# CE842170047_SHEET2.net
KiCad netlist of a schematic drawn in Altium Designer
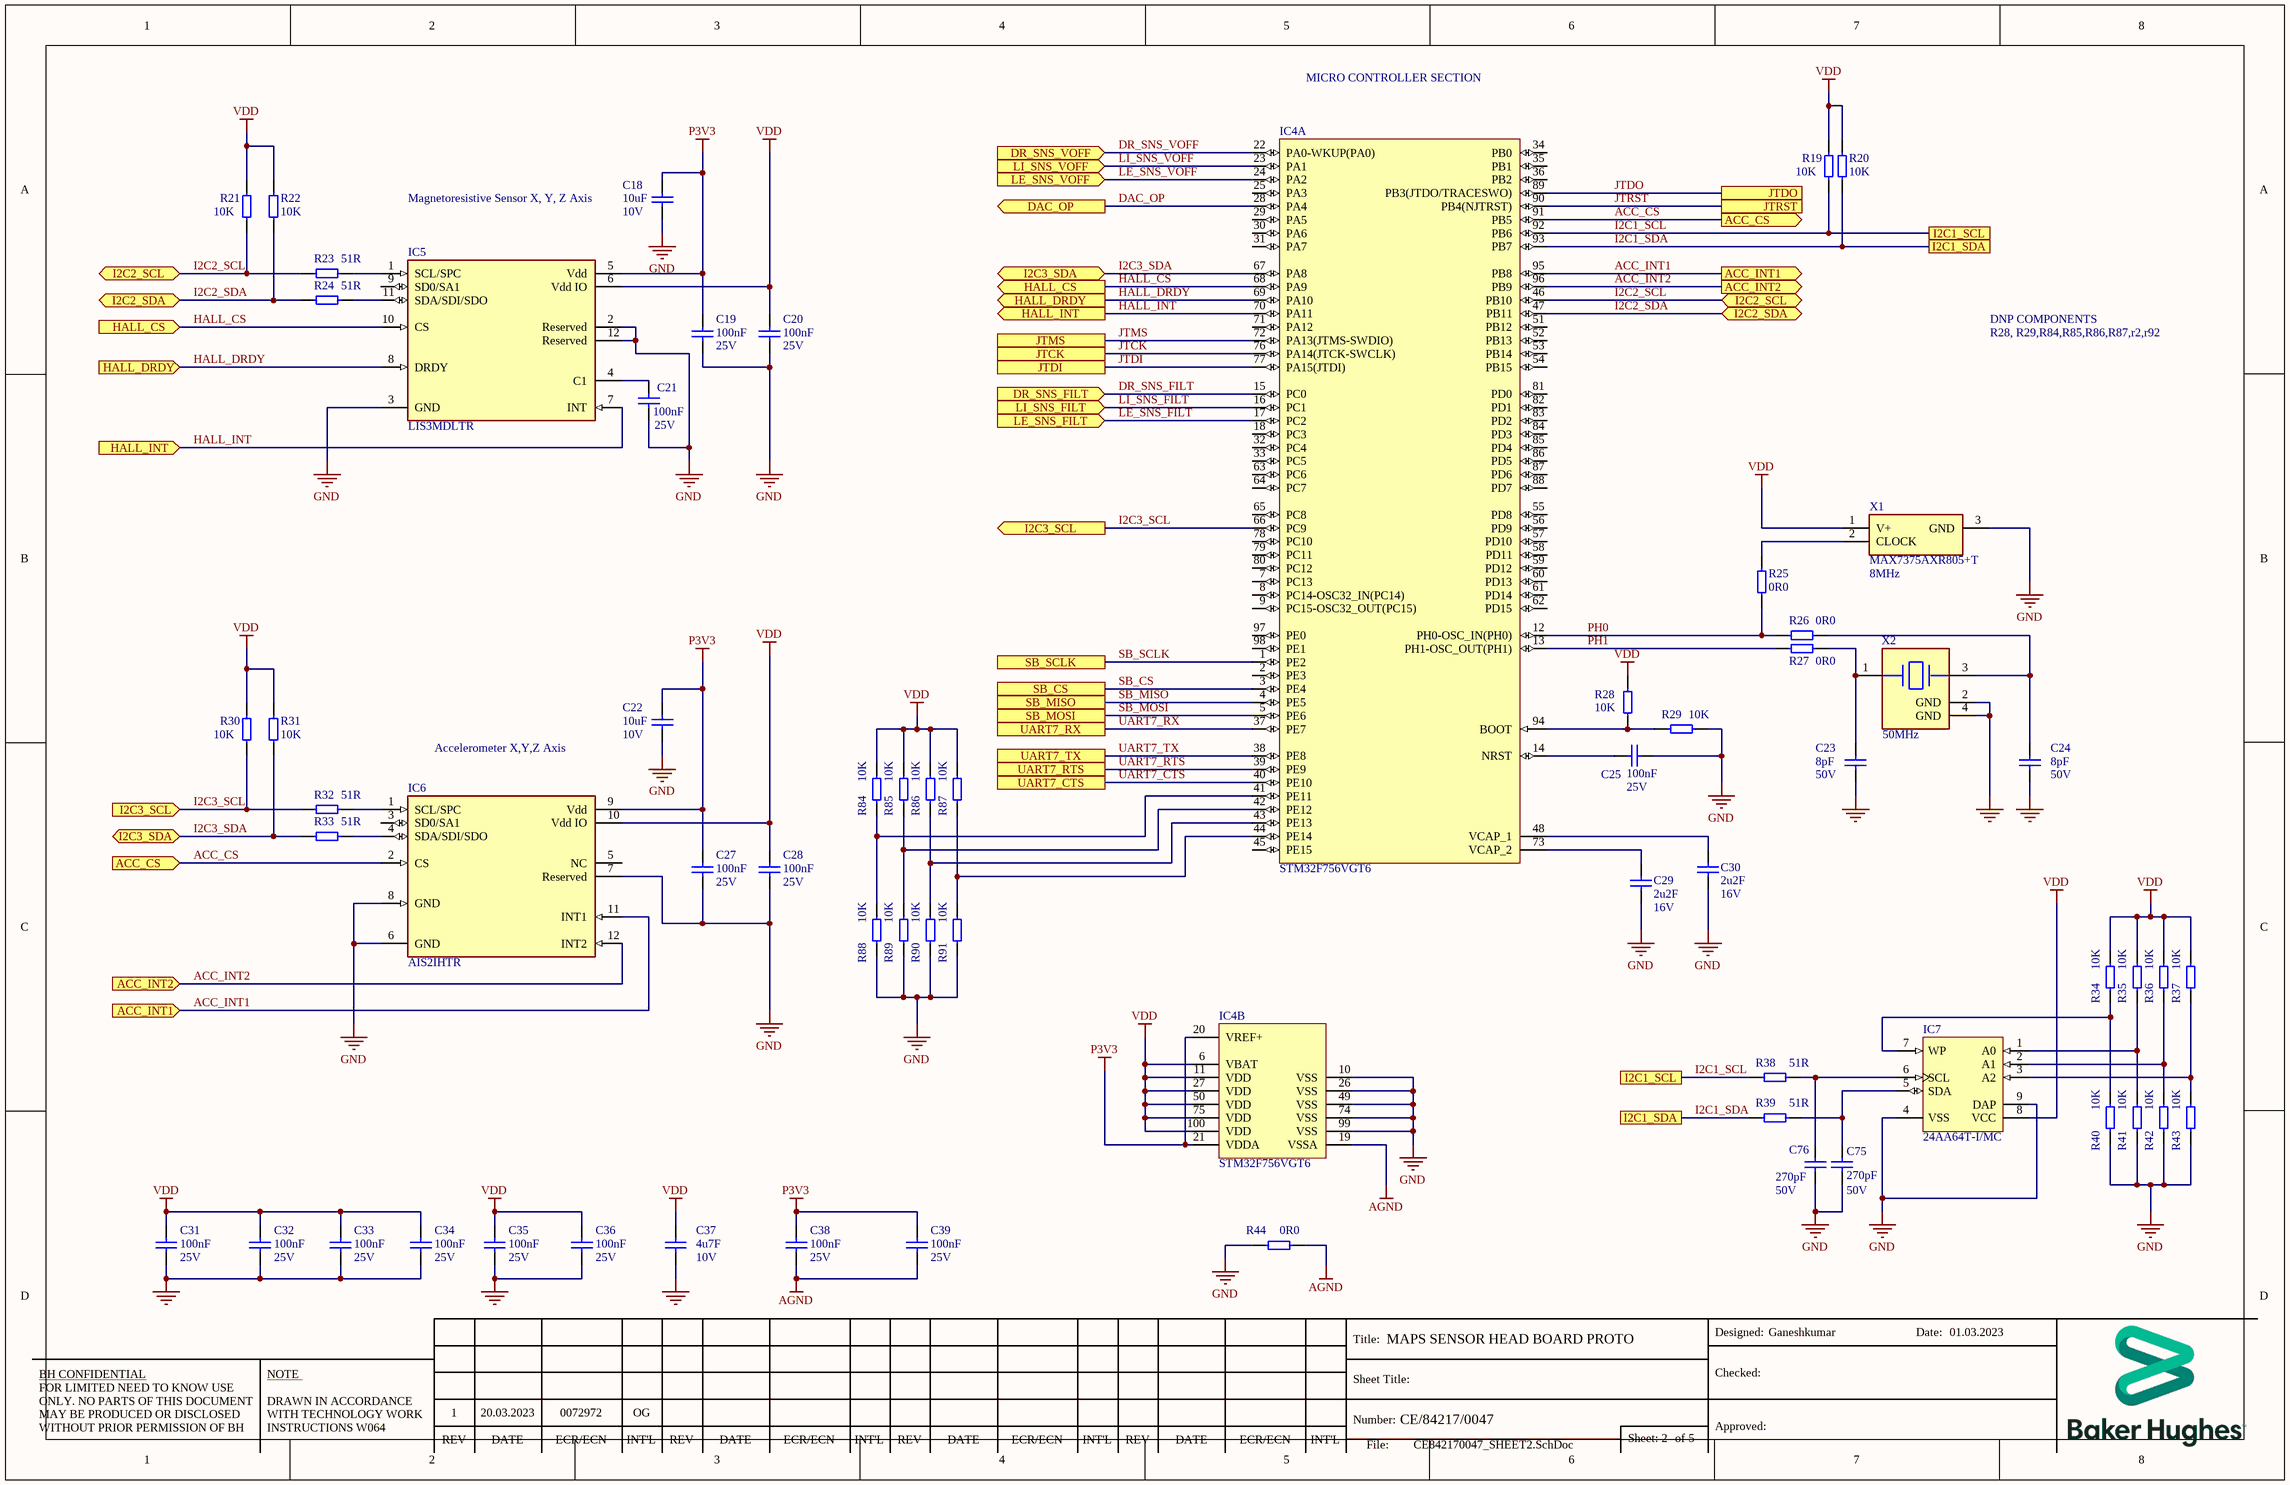
[diagram p0: CE842170047_SHEET2.SchDoc]

(export (version "E")
  (design (tool "Eeschema 10.0.6"))
  (components
    (comp (ref "C18")
      (value "10uF")
      (footprint "C0603")
      (description "CAPACITOR_10uF_10%_10V_0603")
      (fields
        (field (name "VOLTAGE") "10V")
        (field (name "PII_PARTNUMBER") "KK/96159/3701")
        (field (name "TOLERANCE") "10%")
      )
      (libsource (lib "AltiumComponents") (part "CAP_GENERIC"))
    )
    (comp (ref "C19")
      (value "100nF")
      (footprint "C0603")
      (description "CAPACITOR_100nF_+10%_25V_603")
      (fields
        (field (name "VOLTAGE") "25V")
        (field (name "PII_PARTNUMBER") "KK/96159/4501")
        (field (name "TOLERANCE") "10%")
      )
      (libsource (lib "AltiumComponents") (part "CAP_GENERIC"))
    )
    (comp (ref "C20")
      (value "100nF")
      (footprint "C0603")
      (description "CAPACITOR_100nF_+10%_25V_603")
      (fields
        (field (name "VOLTAGE") "25V")
        (field (name "PII_PARTNUMBER") "KK/96159/4501")
        (field (name "TOLERANCE") "10%")
      )
      (libsource (lib "AltiumComponents") (part "CAP_GENERIC"))
    )
    (comp (ref "C21")
      (value "100nF")
      (footprint "C0603")
      (description "CAPACITOR_100nF_+10%_25V_603")
      (fields
        (field (name "VOLTAGE") "25V")
        (field (name "PII_PARTNUMBER") "KK/96159/4501")
        (field (name "TOLERANCE") "10%")
      )
      (libsource (lib "AltiumComponents") (part "CAP_GENERIC"))
    )
    (comp (ref "C22")
      (value "10uF")
      (footprint "C0603")
      (description "CAPACITOR_10uF_10%_10V_0603")
      (fields
        (field (name "VOLTAGE") "10V")
        (field (name "PII_PARTNUMBER") "KK/96159/3701")
        (field (name "TOLERANCE") "10%")
      )
      (libsource (lib "AltiumComponents") (part "CAP_GENERIC"))
    )
    (comp (ref "C23")
      (value "8pF")
      (footprint "C0603")
      (description "CAPACITOR CERAMIC 0603 50V 5% NPO 8pF")
      (fields
        (field (name "VOLTAGE") "50V")
        (field (name "PII_PARTNUMBER") "KK/96159/0088")
        (field (name "TOLERANCE") "5%")
      )
      (libsource (lib "AltiumComponents") (part "CAP_GENERIC"))
    )
    (comp (ref "C24")
      (value "8pF")
      (footprint "C0603")
      (description "CAPACITOR CERAMIC 0603 50V 5% NPO 8pF")
      (fields
        (field (name "VOLTAGE") "50V")
        (field (name "PII_PARTNUMBER") "KK/96159/0088")
        (field (name "TOLERANCE") "5%")
      )
      (libsource (lib "AltiumComponents") (part "CAP_GENERIC"))
    )
    (comp (ref "C25")
      (value "100nF")
      (footprint "C0603")
      (description "CAPACITOR_100nF_+10%_25V_603")
      (fields
        (field (name "VOLTAGE") "25V")
        (field (name "PII_PARTNUMBER") "KK/96159/4501")
        (field (name "TOLERANCE") "10%")
      )
      (libsource (lib "AltiumComponents") (part "CAP_GENERIC"))
    )
    (comp (ref "C27")
      (value "100nF")
      (footprint "C0603")
      (description "CAPACITOR_100nF_+10%_25V_603")
      (fields
        (field (name "VOLTAGE") "25V")
        (field (name "PII_PARTNUMBER") "KK/96159/4501")
        (field (name "TOLERANCE") "10%")
      )
      (libsource (lib "AltiumComponents") (part "CAP_GENERIC"))
    )
    (comp (ref "C28")
      (value "100nF")
      (footprint "C0603")
      (description "CAPACITOR_100nF_+10%_25V_603")
      (fields
        (field (name "VOLTAGE") "25V")
        (field (name "PII_PARTNUMBER") "KK/96159/4501")
        (field (name "TOLERANCE") "10%")
      )
      (libsource (lib "AltiumComponents") (part "CAP_GENERIC"))
    )
    (comp (ref "C29")
      (value "2u2F")
      (footprint "C0603")
      (description "CAPACITOR CERAMIC 0603 16V 10% X5R 2u2")
      (fields
        (field (name "VOLTAGE") "16V")
        (field (name "PII_PARTNUMBER") "KK/96159/3634")
        (field (name "TOLERANCE") "10%")
      )
      (libsource (lib "AltiumComponents") (part "CAP_GENERIC"))
    )
    (comp (ref "C30")
      (value "2u2F")
      (footprint "C0603")
      (description "CAPACITOR CERAMIC 0603 16V 10% X5R 2u2")
      (fields
        (field (name "VOLTAGE") "16V")
        (field (name "PII_PARTNUMBER") "KK/96159/3634")
        (field (name "TOLERANCE") "10%")
      )
      (libsource (lib "AltiumComponents") (part "CAP_GENERIC"))
    )
    (comp (ref "C31")
      (value "100nF")
      (footprint "C0603")
      (description "CAPACITOR_100nF_+10%_25V_603")
      (fields
        (field (name "VOLTAGE") "25V")
        (field (name "PII_PARTNUMBER") "KK/96159/4501")
        (field (name "TOLERANCE") "10%")
      )
      (libsource (lib "AltiumComponents") (part "CAP_GENERIC"))
    )
    (comp (ref "C32")
      (value "100nF")
      (footprint "C0603")
      (description "CAPACITOR_100nF_+10%_25V_603")
      (fields
        (field (name "VOLTAGE") "25V")
        (field (name "PII_PARTNUMBER") "KK/96159/4501")
        (field (name "TOLERANCE") "10%")
      )
      (libsource (lib "AltiumComponents") (part "CAP_GENERIC"))
    )
    (comp (ref "C33")
      (value "100nF")
      (footprint "C0603")
      (description "CAPACITOR_100nF_+10%_25V_603")
      (fields
        (field (name "VOLTAGE") "25V")
        (field (name "PII_PARTNUMBER") "KK/96159/4501")
        (field (name "TOLERANCE") "10%")
      )
      (libsource (lib "AltiumComponents") (part "CAP_GENERIC"))
    )
    (comp (ref "C34")
      (value "100nF")
      (footprint "C0603")
      (description "CAPACITOR_100nF_+10%_25V_603")
      (fields
        (field (name "VOLTAGE") "25V")
        (field (name "PII_PARTNUMBER") "KK/96159/4501")
        (field (name "TOLERANCE") "10%")
      )
      (libsource (lib "AltiumComponents") (part "CAP_GENERIC"))
    )
    (comp (ref "C35")
      (value "100nF")
      (footprint "C0603")
      (description "CAPACITOR_100nF_+10%_25V_603")
      (fields
        (field (name "VOLTAGE") "25V")
        (field (name "PII_PARTNUMBER") "KK/96159/4501")
        (field (name "TOLERANCE") "10%")
      )
      (libsource (lib "AltiumComponents") (part "CAP_GENERIC"))
    )
    (comp (ref "C36")
      (value "100nF")
      (footprint "C0603")
      (description "CAPACITOR_100nF_+10%_25V_603")
      (fields
        (field (name "VOLTAGE") "25V")
        (field (name "PII_PARTNUMBER") "KK/96159/4501")
        (field (name "TOLERANCE") "10%")
      )
      (libsource (lib "AltiumComponents") (part "CAP_GENERIC"))
    )
    (comp (ref "C37")
      (value "4u7F")
      (footprint "C0603")
      (description "CAPACITOR_4u7F_10%_10V_0603")
      (fields
        (field (name "VOLTAGE") "10V")
        (field (name "PII_PARTNUMBER") "KK/96159/2666")
        (field (name "TOLERANCE") "10%")
      )
      (libsource (lib "AltiumComponents") (part "CAP_GENERIC"))
    )
    (comp (ref "C38")
      (value "100nF")
      (footprint "C0603")
      (description "CAPACITOR_100nF_+10%_25V_603")
      (fields
        (field (name "VOLTAGE") "25V")
        (field (name "PII_PARTNUMBER") "KK/96159/4501")
        (field (name "TOLERANCE") "10%")
      )
      (libsource (lib "AltiumComponents") (part "CAP_GENERIC"))
    )
    (comp (ref "C39")
      (value "100nF")
      (footprint "C0603")
      (description "CAPACITOR_100nF_+10%_25V_603")
      (fields
        (field (name "VOLTAGE") "25V")
        (field (name "PII_PARTNUMBER") "KK/96159/4501")
        (field (name "TOLERANCE") "10%")
      )
      (libsource (lib "AltiumComponents") (part "CAP_GENERIC"))
    )
    (comp (ref "C75")
      (value "270pF")
      (footprint "C0603")
      (description "CAPACITOR CER 0603 270pF 10% 50V X5R")
      (fields
        (field (name "VOLTAGE") "50V")
        (field (name "PII_PARTNUMBER") "KK/96159/0243")
        (field (name "TOLERANCE") "10%")
      )
      (libsource (lib "AltiumComponents") (part "CAP_GENERIC"))
    )
    (comp (ref "C76")
      (value "270pF")
      (footprint "C0603")
      (description "CAPACITOR CER 0603 270pF 10% 50V X5R")
      (fields
        (field (name "VOLTAGE") "50V")
        (field (name "PII_PARTNUMBER") "KK/96159/0243")
        (field (name "TOLERANCE") "10%")
      )
      (libsource (lib "AltiumComponents") (part "CAP_GENERIC"))
    )
    (comp (ref "IC4")
      (value "KK/95414/0147")
      (footprint "LQFP-100")
      (description "MICROCONTROLLER MCU")
      (fields
        (field (name "MANUFACTURER") "STMICROELECTRONICS")
        (field (name "MANUFACTURER PART NUMBER") "STM32F756VGT6")
        (field (name "MF_PARTNUMBER") "STM32F756VGT6")
      )
      (libsource (lib "AltiumComponents") (part "STM32F756"))
    )
    (comp (ref "IC5")
      (value "KK/95312/0195")
      (footprint "LGA-12")
      (description "3 AXIS MAGNETIC SENSOR")
      (fields
        (field (name "MANUFACTURER PART NUMBER") "LIS3MDLTR")
        (field (name "OCTOPART") "https://octopart.com/lis3mdltr-stmicroelectronics-29403125")
        (field (name "MF_PARTNUMBER") "LIS3MDLTR")
      )
      (libsource (lib "AltiumComponents") (part "LIS3MDL"))
    )
    (comp (ref "IC6")
      (value "KK/95312/0196")
      (footprint "LGA-12")
      (description "3 AXIS DIGITAL ACCELEROMETER 14BIT")
      (fields
        (field (name "OCTOPART") "https://www.mouser.co.uk/datasheet/2/389/dm00462829-2042226.pdf")
        (field (name "MANUFACTURER") "STMicroelectronics")
        (field (name "MF_PARTNUMBER") "AIS2IHTR")
      )
      (libsource (lib "AltiumComponents") (part "AIS2IH"))
    )
    (comp (ref "IC7")
      (value "KK/95413/0138")
      (footprint "DFN-8")
      (description "64K I2C SERIAL EEPROM")
      (fields
        (field (name "MANUFACTURER") "MICROCHIP")
        (field (name "MANUFACTURER PART NUMBER") "24AA64T-I/MC")
        (field (name "MF_PARTNUMBER") "24AA64T-I/MC")
      )
      (libsource (lib "AltiumComponents") (part "24AA64_9PIN"))
    )
    (comp (ref "R19")
      (value "10K")
      (footprint "R0603")
      (description "RESISTOR_10K_1%_0603J_63mW")
      (fields (field (name "PII_PARTNUMBER") "KK/96059/0601") (field (name "TOLERANCE") "1%"))
      (libsource (lib "AltiumComponents") (part "RES_GENERIC"))
    )
    (comp (ref "R20")
      (value "10K")
      (footprint "R0603")
      (description "RESISTOR_10K_1%_0603J_63mW")
      (fields (field (name "PII_PARTNUMBER") "KK/96059/0601") (field (name "TOLERANCE") "1%"))
      (libsource (lib "AltiumComponents") (part "RES_GENERIC"))
    )
    (comp (ref "R21")
      (value "10K")
      (footprint "R0603")
      (description "RESISTOR_10K_1%_0603J_63mW")
      (fields (field (name "PII_PARTNUMBER") "KK/96059/0601") (field (name "TOLERANCE") "1%"))
      (libsource (lib "AltiumComponents") (part "RES_GENERIC"))
    )
    (comp (ref "R22")
      (value "10K")
      (footprint "R0603")
      (description "RESISTOR_10K_1%_0603J_63mW")
      (fields (field (name "PII_PARTNUMBER") "KK/96059/0601") (field (name "TOLERANCE") "1%"))
      (libsource (lib "AltiumComponents") (part "RES_GENERIC"))
    )
    (comp (ref "R23")
      (value "51R")
      (footprint "R0603")
      (description "RESISTOR_51R_1%_0603J_63mW")
      (fields (field (name "PII_PARTNUMBER") "KK/96059/1369") (field (name "TOLERANCE") "1%"))
      (libsource (lib "") (part "RES_GENERIC_1"))
    )
    (comp (ref "R24")
      (value "51R")
      (footprint "R0603")
      (description "RESISTOR_51R_1%_0603J_63mW")
      (fields (field (name "PII_PARTNUMBER") "KK/96059/1369") (field (name "TOLERANCE") "1%"))
      (libsource (lib "") (part "RES_GENERIC_1"))
    )
    (comp (ref "R25")
      (value "0R0")
      (footprint "R0603")
      (description "ZERO OHM LINK")
      (fields (field (name "PII_PARTNUMBER") "KK/96059/0000") (field (name "POWER") "63mW"))
      (libsource (lib "") (part "RES_GENERIC_3"))
    )
    (comp (ref "R26")
      (value "0R0")
      (footprint "R0603")
      (description "ZERO OHM LINK")
      (fields (field (name "PII_PARTNUMBER") "KK/96059/0000") (field (name "POWER") "63mW"))
      (libsource (lib "") (part "RES_GENERIC_1"))
    )
    (comp (ref "R27")
      (value "0R0")
      (footprint "R0603")
      (description "ZERO OHM LINK")
      (fields (field (name "PII_PARTNUMBER") "KK/96059/0000") (field (name "POWER") "63mW"))
      (libsource (lib "") (part "RES_GENERIC_1"))
    )
    (comp (ref "R28")
      (value "10K")
      (footprint "R0603")
      (description "RESISTOR_10K_1%_0603J_63mW")
      (fields (field (name "PII_PARTNUMBER") "KK/96059/0601") (field (name "TOLERANCE") "1%"))
      (libsource (lib "AltiumComponents") (part "RES_GENERIC"))
    )
    (comp (ref "R29")
      (value "10K")
      (footprint "R0603")
      (description "RESISTOR_10K_1%_0603J_63mW")
      (fields (field (name "PII_PARTNUMBER") "KK/96059/0601") (field (name "TOLERANCE") "1%"))
      (libsource (lib "") (part "RES_GENERIC_2"))
    )
    (comp (ref "R30")
      (value "10K")
      (footprint "R0603")
      (description "RESISTOR_10K_1%_0603J_63mW")
      (fields (field (name "PII_PARTNUMBER") "KK/96059/0601") (field (name "TOLERANCE") "1%"))
      (libsource (lib "AltiumComponents") (part "RES_GENERIC"))
    )
    (comp (ref "R31")
      (value "10K")
      (footprint "R0603")
      (description "RESISTOR_10K_1%_0603J_63mW")
      (fields (field (name "PII_PARTNUMBER") "KK/96059/0601") (field (name "TOLERANCE") "1%"))
      (libsource (lib "AltiumComponents") (part "RES_GENERIC"))
    )
    (comp (ref "R32")
      (value "51R")
      (footprint "R0603")
      (description "RESISTOR_51R_1%_0603J_63mW")
      (fields (field (name "PII_PARTNUMBER") "KK/96059/1369") (field (name "TOLERANCE") "1%"))
      (libsource (lib "") (part "RES_GENERIC_1"))
    )
    (comp (ref "R33")
      (value "51R")
      (footprint "R0603")
      (description "RESISTOR_51R_1%_0603J_63mW")
      (fields (field (name "PII_PARTNUMBER") "KK/96059/1369") (field (name "TOLERANCE") "1%"))
      (libsource (lib "") (part "RES_GENERIC_1"))
    )
    (comp (ref "R34")
      (value "10K")
      (footprint "R0603")
      (description "RESISTOR_10K_1%_0603J_63mW")
      (fields (field (name "PII_PARTNUMBER") "KK/96059/0601") (field (name "TOLERANCE") "1%"))
      (libsource (lib "") (part "RES_GENERIC_2"))
    )
    (comp (ref "R35")
      (value "10K")
      (footprint "R0603")
      (description "RESISTOR_10K_1%_0603J_63mW")
      (fields (field (name "PII_PARTNUMBER") "KK/96059/0601") (field (name "TOLERANCE") "1%"))
      (libsource (lib "") (part "RES_GENERIC_2"))
    )
    (comp (ref "R36")
      (value "10K")
      (footprint "R0603")
      (description "RESISTOR_10K_1%_0603J_63mW")
      (fields (field (name "PII_PARTNUMBER") "KK/96059/0601") (field (name "TOLERANCE") "1%"))
      (libsource (lib "") (part "RES_GENERIC_2"))
    )
    (comp (ref "R37")
      (value "10K")
      (footprint "R0603")
      (description "RESISTOR_10K_1%_0603J_63mW")
      (fields (field (name "PII_PARTNUMBER") "KK/96059/0601") (field (name "TOLERANCE") "1%"))
      (libsource (lib "") (part "RES_GENERIC_2"))
    )
    (comp (ref "R38")
      (value "51R")
      (footprint "R0603")
      (description "RESISTOR_51R_1%_0603J_63mW")
      (fields (field (name "PII_PARTNUMBER") "KK/96059/1369") (field (name "TOLERANCE") "1%"))
      (libsource (lib "AltiumComponents") (part "RES_GENERIC"))
    )
    (comp (ref "R39")
      (value "51R")
      (footprint "R0603")
      (description "RESISTOR_51R_1%_0603J_63mW")
      (fields (field (name "PII_PARTNUMBER") "KK/96059/1369") (field (name "TOLERANCE") "1%"))
      (libsource (lib "AltiumComponents") (part "RES_GENERIC"))
    )
    (comp (ref "R40")
      (value "10K")
      (footprint "R0603")
      (description "RESISTOR_10K_1%_0603J_63mW")
      (fields (field (name "PII_PARTNUMBER") "KK/96059/0601") (field (name "TOLERANCE") "1%"))
      (libsource (lib "") (part "RES_GENERIC_2"))
    )
    (comp (ref "R41")
      (value "10K")
      (footprint "R0603")
      (description "RESISTOR_10K_1%_0603J_63mW")
      (fields (field (name "PII_PARTNUMBER") "KK/96059/0601") (field (name "TOLERANCE") "1%"))
      (libsource (lib "") (part "RES_GENERIC_2"))
    )
    (comp (ref "R42")
      (value "10K")
      (footprint "R0603")
      (description "RESISTOR_10K_1%_0603J_63mW")
      (fields (field (name "PII_PARTNUMBER") "KK/96059/0601") (field (name "TOLERANCE") "1%"))
      (libsource (lib "") (part "RES_GENERIC_2"))
    )
    (comp (ref "R43")
      (value "10K")
      (footprint "R0603")
      (description "RESISTOR_10K_1%_0603J_63mW")
      (fields (field (name "PII_PARTNUMBER") "KK/96059/0601") (field (name "TOLERANCE") "1%"))
      (libsource (lib "") (part "RES_GENERIC_2"))
    )
    (comp (ref "R44")
      (value "0R0")
      (footprint "R0603")
      (description "ZERO OHM LINK")
      (fields (field (name "PII_PARTNUMBER") "KK/96059/0000") (field (name "POWER") "63mW"))
      (libsource (lib "") (part "RES_GENERIC_1"))
    )
    (comp (ref "R84")
      (value "10K")
      (footprint "R0603")
      (description "RESISTOR_10K_1%_0603J_63mW")
      (fields (field (name "PII_PARTNUMBER") "KK/96059/0601") (field (name "TOLERANCE") "1%"))
      (libsource (lib "") (part "RES_GENERIC_2"))
    )
    (comp (ref "R85")
      (value "10K")
      (footprint "R0603")
      (description "RESISTOR_10K_1%_0603J_63mW")
      (fields (field (name "PII_PARTNUMBER") "KK/96059/0601") (field (name "TOLERANCE") "1%"))
      (libsource (lib "") (part "RES_GENERIC_2"))
    )
    (comp (ref "R86")
      (value "10K")
      (footprint "R0603")
      (description "RESISTOR_10K_1%_0603J_63mW")
      (fields (field (name "PII_PARTNUMBER") "KK/96059/0601") (field (name "TOLERANCE") "1%"))
      (libsource (lib "") (part "RES_GENERIC_2"))
    )
    (comp (ref "R87")
      (value "10K")
      (footprint "R0603")
      (description "RESISTOR_10K_1%_0603J_63mW")
      (fields (field (name "PII_PARTNUMBER") "KK/96059/0601") (field (name "TOLERANCE") "1%"))
      (libsource (lib "") (part "RES_GENERIC_2"))
    )
    (comp (ref "R88")
      (value "10K")
      (footprint "R0603")
      (description "RESISTOR_10K_1%_0603J_63mW")
      (fields (field (name "PII_PARTNUMBER") "KK/96059/0601") (field (name "TOLERANCE") "1%"))
      (libsource (lib "") (part "RES_GENERIC_2"))
    )
    (comp (ref "R89")
      (value "10K")
      (footprint "R0603")
      (description "RESISTOR_10K_1%_0603J_63mW")
      (fields (field (name "PII_PARTNUMBER") "KK/96059/0601") (field (name "TOLERANCE") "1%"))
      (libsource (lib "") (part "RES_GENERIC_2"))
    )
    (comp (ref "R90")
      (value "10K")
      (footprint "R0603")
      (description "RESISTOR_10K_1%_0603J_63mW")
      (fields (field (name "PII_PARTNUMBER") "KK/96059/0601") (field (name "TOLERANCE") "1%"))
      (libsource (lib "") (part "RES_GENERIC_2"))
    )
    (comp (ref "R91")
      (value "10K")
      (footprint "R0603")
      (description "RESISTOR_10K_1%_0603J_63mW")
      (fields (field (name "PII_PARTNUMBER") "KK/96059/0601") (field (name "TOLERANCE") "1%"))
      (libsource (lib "") (part "RES_GENERIC_2"))
    )
    (comp (ref "X1")
      (value "8MHz")
      (footprint "SC70-3")
      (description "OSCILLATOR,SMD,CMOS,MAXIM,MAX7375AXR805+T")
      (fields
        (field (name "MF_PARTNUMBER") "MAX7375AXR805+T")
        (field (name "PII_PARTNUMBER") "KK/95710/0303")
        (field (name "VOLTAGE") "2.7-5.5V")
      )
      (libsource (lib "AltiumComponents") (part "OSCILLATOR_3PIN"))
    )
    (comp (ref "X2")
      (value "50MHz")
      (footprint "SMD_1.6X1.2")
      (description "CRYSTAL SMD 50MHz 8pF")
      (fields
        (field (name "MANUFACTURER") "NDK")
        (field (name "MANUFACTURER PART NUMBER") "NX1612SA-50M-EXS00A-CS08403")
      )
      (libsource (lib "AltiumComponents") (part "CRYSTAL_4PIN"))
    )
  )
  (nets
    (net (code "1") (name "/ACC_CS") (class "Default")
      (node (ref "IC4") (pin "91") (pinfunction "PB5_91") (pintype "bidirectional"))
      (node (ref "IC6") (pin "2") (pinfunction "CS_2") (pintype "input"))
    )
    (net (code "2") (name "/ACC_INT1") (class "Default")
      (node (ref "IC4") (pin "95") (pinfunction "PB8_95") (pintype "bidirectional"))
      (node (ref "IC6") (pin "11") (pinfunction "INT1_11") (pintype "input"))
    )
    (net (code "3") (name "/ACC_INT2") (class "Default")
      (node (ref "IC4") (pin "96") (pinfunction "PB9_96") (pintype "bidirectional"))
      (node (ref "IC6") (pin "12") (pinfunction "INT2_12") (pintype "input"))
    )
    (net (code "4") (name "/DAC_OP") (class "Default")
      (node (ref "IC4") (pin "28") (pinfunction "PA4_28") (pintype "bidirectional"))
    )
    (net (code "5") (name "/DR_SNS_FILT") (class "Default")
      (node (ref "IC4") (pin "15") (pinfunction "PC0_15") (pintype "bidirectional"))
    )
    (net (code "6") (name "/DR_SNS_VOFF") (class "Default")
      (node (ref "IC4") (pin "22") (pinfunction "PA0-WKUP(PA0)_22") (pintype "bidirectional"))
    )
    (net (code "7") (name "/HALL_CS") (class "Default")
      (node (ref "IC4") (pin "68") (pinfunction "PA9_68") (pintype "bidirectional"))
      (node (ref "IC5") (pin "10") (pinfunction "CS_10") (pintype "input"))
    )
    (net (code "8") (name "/HALL_DRDY") (class "Default")
      (node (ref "IC4") (pin "69") (pinfunction "PA10_69") (pintype "bidirectional"))
      (node (ref "IC5") (pin "8") (pinfunction "DRDY_8") (pintype "input"))
    )
    (net (code "9") (name "/HALL_INT") (class "Default")
      (node (ref "IC4") (pin "70") (pinfunction "PA11_70") (pintype "bidirectional"))
      (node (ref "IC5") (pin "7") (pinfunction "INT_7") (pintype "input"))
    )
    (net (code "10") (name "/I2C1_SCL") (class "Default")
      (node (ref "IC4") (pin "92") (pinfunction "PB6_92") (pintype "bidirectional"))
      (node (ref "R19") (pin "1") (pinfunction "1_1") (pintype "passive"))
      (node (ref "R38") (pin "1") (pinfunction "1_1") (pintype "passive"))
    )
    (net (code "11") (name "/I2C1_SDA") (class "Default")
      (node (ref "IC4") (pin "93") (pinfunction "PB7_93") (pintype "bidirectional"))
      (node (ref "R20") (pin "1") (pinfunction "1_1") (pintype "passive"))
      (node (ref "R39") (pin "1") (pinfunction "1_1") (pintype "passive"))
    )
    (net (code "12") (name "/I2C2_SCL") (class "Default")
      (node (ref "IC4") (pin "46") (pinfunction "PB10_46") (pintype "bidirectional"))
      (node (ref "R21") (pin "1") (pinfunction "1_1") (pintype "passive"))
      (node (ref "R23") (pin "1") (pinfunction "1_1") (pintype "passive"))
    )
    (net (code "13") (name "/I2C2_SDA") (class "Default")
      (node (ref "IC4") (pin "47") (pinfunction "PB11_47") (pintype "bidirectional"))
      (node (ref "R22") (pin "1") (pinfunction "1_1") (pintype "passive"))
      (node (ref "R24") (pin "1") (pinfunction "1_1") (pintype "passive"))
    )
    (net (code "14") (name "/I2C3_SCL") (class "Default")
      (node (ref "IC4") (pin "66") (pinfunction "PC9_66") (pintype "bidirectional"))
      (node (ref "R30") (pin "1") (pinfunction "1_1") (pintype "passive"))
      (node (ref "R32") (pin "1") (pinfunction "1_1") (pintype "passive"))
    )
    (net (code "15") (name "/I2C3_SDA") (class "Default")
      (node (ref "IC4") (pin "67") (pinfunction "PA8_67") (pintype "bidirectional"))
      (node (ref "R31") (pin "1") (pinfunction "1_1") (pintype "passive"))
      (node (ref "R33") (pin "1") (pinfunction "1_1") (pintype "passive"))
    )
    (net (code "16") (name "/JTCK") (class "Default")
      (node (ref "IC4") (pin "76") (pinfunction "PA14(JTCK-SWCLK)_76") (pintype "bidirectional"))
    )
    (net (code "17") (name "/JTDI") (class "Default")
      (node (ref "IC4") (pin "77") (pinfunction "PA15(JTDI)_77") (pintype "bidirectional"))
    )
    (net (code "18") (name "/JTDO") (class "Default")
      (node (ref "IC4") (pin "89") (pinfunction "PB3(JTDO/TRACESWO)_89") (pintype "bidirectional"))
    )
    (net (code "19") (name "/JTMS") (class "Default")
      (node (ref "IC4") (pin "72") (pinfunction "PA13(JTMS-SWDIO)_72") (pintype "bidirectional"))
    )
    (net (code "20") (name "/JTRST") (class "Default")
      (node (ref "IC4") (pin "90") (pinfunction "PB4(NJTRST)_90") (pintype "bidirectional"))
    )
    (net (code "21") (name "/LE_SNS_FILT") (class "Default")
      (node (ref "IC4") (pin "17") (pinfunction "PC2_17") (pintype "bidirectional"))
    )
    (net (code "22") (name "/LE_SNS_VOFF") (class "Default")
      (node (ref "IC4") (pin "24") (pinfunction "PA2_24") (pintype "bidirectional"))
    )
    (net (code "23") (name "/LI_SNS_FILT") (class "Default")
      (node (ref "IC4") (pin "16") (pinfunction "PC1_16") (pintype "bidirectional"))
    )
    (net (code "24") (name "/LI_SNS_VOFF") (class "Default")
      (node (ref "IC4") (pin "23") (pinfunction "PA1_23") (pintype "bidirectional"))
    )
    (net (code "25") (name "/PH0") (class "Default")
      (node (ref "IC4") (pin "12") (pinfunction "PH0-OSC_IN(PH0)_12") (pintype "bidirectional"))
      (node (ref "R25") (pin "2") (pinfunction "2_2") (pintype "passive"))
      (node (ref "R26") (pin "1") (pinfunction "1_1") (pintype "passive"))
    )
    (net (code "26") (name "/PH1") (class "Default")
      (node (ref "IC4") (pin "13") (pinfunction "PH1-OSC_OUT(PH1)_13") (pintype "bidirectional"))
      (node (ref "R27") (pin "1") (pinfunction "1_1") (pintype "passive"))
    )
    (net (code "27") (name "/SB_CS") (class "Default")
      (node (ref "IC4") (pin "3") (pinfunction "PE4_3") (pintype "bidirectional"))
    )
    (net (code "28") (name "/SB_MISO") (class "Default")
      (node (ref "IC4") (pin "4") (pinfunction "PE5_4") (pintype "bidirectional"))
    )
    (net (code "29") (name "/SB_MOSI") (class "Default")
      (node (ref "IC4") (pin "5") (pinfunction "PE6_5") (pintype "bidirectional"))
    )
    (net (code "30") (name "/SB_SCLK") (class "Default")
      (node (ref "IC4") (pin "1") (pinfunction "PE2_1") (pintype "bidirectional"))
    )
    (net (code "31") (name "/UART7_CTS") (class "Default")
      (node (ref "IC4") (pin "40") (pinfunction "PE10_40") (pintype "bidirectional"))
    )
    (net (code "32") (name "/UART7_RTS") (class "Default")
      (node (ref "IC4") (pin "39") (pinfunction "PE9_39") (pintype "bidirectional"))
    )
    (net (code "33") (name "/UART7_RX") (class "Default")
      (node (ref "IC4") (pin "37") (pinfunction "PE7_37") (pintype "bidirectional"))
    )
    (net (code "34") (name "/UART7_TX") (class "Default")
      (node (ref "IC4") (pin "38") (pinfunction "PE8_38") (pintype "bidirectional"))
    )
    (net (code "35") (name "AGND") (class "Default")
      (node (ref "C38") (pin "2") (pinfunction "2_2") (pintype "passive"))
      (node (ref "C39") (pin "2") (pinfunction "2_2") (pintype "passive"))
      (node (ref "IC4") (pin "19") (pinfunction "VSSA_19") (pintype "power_in"))
      (node (ref "R44") (pin "2") (pinfunction "2_2") (pintype "passive"))
    )
    (net (code "36") (name "GND") (class "Default")
      (node (ref "C18") (pin "2") (pinfunction "2_2") (pintype "passive"))
      (node (ref "C19") (pin "2") (pinfunction "2_2") (pintype "passive"))
      (node (ref "C20") (pin "2") (pinfunction "2_2") (pintype "passive"))
      (node (ref "C21") (pin "2") (pinfunction "2_2") (pintype "passive"))
      (node (ref "C22") (pin "2") (pinfunction "2_2") (pintype "passive"))
      (node (ref "C23") (pin "2") (pinfunction "2_2") (pintype "passive"))
      (node (ref "C24") (pin "1") (pinfunction "1_1") (pintype "passive"))
      (node (ref "C25") (pin "2") (pinfunction "2_2") (pintype "passive"))
      (node (ref "C27") (pin "2") (pinfunction "2_2") (pintype "passive"))
      (node (ref "C28") (pin "2") (pinfunction "2_2") (pintype "passive"))
      (node (ref "C29") (pin "2") (pinfunction "2_2") (pintype "passive"))
      (node (ref "C30") (pin "2") (pinfunction "2_2") (pintype "passive"))
      (node (ref "C31") (pin "2") (pinfunction "2_2") (pintype "passive"))
      (node (ref "C32") (pin "2") (pinfunction "2_2") (pintype "passive"))
      (node (ref "C33") (pin "2") (pinfunction "2_2") (pintype "passive"))
      (node (ref "C34") (pin "2") (pinfunction "2_2") (pintype "passive"))
      (node (ref "C35") (pin "2") (pinfunction "2_2") (pintype "passive"))
      (node (ref "C36") (pin "2") (pinfunction "2_2") (pintype "passive"))
      (node (ref "C37") (pin "2") (pinfunction "2_2") (pintype "passive"))
      (node (ref "C75") (pin "2") (pinfunction "2_2") (pintype "passive"))
      (node (ref "C76") (pin "2") (pinfunction "2_2") (pintype "passive"))
      (node (ref "IC4") (pin "10") (pinfunction "VSS_10") (pintype "power_in"))
      (node (ref "IC4") (pin "26") (pinfunction "VSS_26") (pintype "power_in"))
      (node (ref "IC4") (pin "49") (pinfunction "VSS_49") (pintype "power_in"))
      (node (ref "IC4") (pin "74") (pinfunction "VSS_74") (pintype "power_in"))
      (node (ref "IC4") (pin "99") (pinfunction "VSS_99") (pintype "power_in"))
      (node (ref "IC5") (pin "12") (pinfunction "Reserved_12") (pintype "passive"))
      (node (ref "IC5") (pin "2") (pinfunction "Reserved_2") (pintype "passive"))
      (node (ref "IC5") (pin "3") (pinfunction "GND_3") (pintype "power_in"))
      (node (ref "IC6") (pin "6") (pinfunction "GND_6") (pintype "power_in"))
      (node (ref "IC6") (pin "7") (pinfunction "Reserved_7") (pintype "passive"))
      (node (ref "IC6") (pin "8") (pinfunction "GND_8") (pintype "input"))
      (node (ref "IC7") (pin "4") (pinfunction "VSS_4") (pintype "power_in"))
      (node (ref "IC7") (pin "9") (pinfunction "DAP_9") (pintype "power_in"))
      (node (ref "R29") (pin "1") (pinfunction "1_1") (pintype "passive"))
      (node (ref "R40") (pin "2") (pinfunction "2_2") (pintype "passive"))
      (node (ref "R41") (pin "2") (pinfunction "2_2") (pintype "passive"))
      (node (ref "R42") (pin "2") (pinfunction "2_2") (pintype "passive"))
      (node (ref "R43") (pin "2") (pinfunction "2_2") (pintype "passive"))
      (node (ref "R44") (pin "1") (pinfunction "1_1") (pintype "passive"))
      (node (ref "R88") (pin "2") (pinfunction "2_2") (pintype "passive"))
      (node (ref "R89") (pin "2") (pinfunction "2_2") (pintype "passive"))
      (node (ref "R90") (pin "2") (pinfunction "2_2") (pintype "passive"))
      (node (ref "R91") (pin "2") (pinfunction "2_2") (pintype "passive"))
      (node (ref "X1") (pin "3") (pinfunction "GND_3") (pintype "passive"))
      (node (ref "X2") (pin "2") (pinfunction "GND_2") (pintype "power_in"))
      (node (ref "X2") (pin "4") (pinfunction "GND_4") (pintype "power_in"))
    )
    (net (code "37") (name "Net-(IC4A-BOOT)") (class "Default")
      (node (ref "IC4") (pin "94") (pinfunction "BOOT_94") (pintype "input"))
      (node (ref "R28") (pin "1") (pinfunction "1_1") (pintype "passive"))
      (node (ref "R29") (pin "2") (pinfunction "2_2") (pintype "passive"))
    )
    (net (code "38") (name "Net-(IC4A-NRST)") (class "Default")
      (node (ref "C25") (pin "1") (pinfunction "1_1") (pintype "passive"))
      (node (ref "IC4") (pin "14") (pinfunction "NRST_14") (pintype "bidirectional"))
    )
    (net (code "39") (name "Net-(IC4A-PE11)") (class "Default")
      (node (ref "IC4") (pin "41") (pinfunction "PE11_41") (pintype "bidirectional"))
      (node (ref "R84") (pin "2") (pinfunction "2_2") (pintype "passive"))
      (node (ref "R88") (pin "1") (pinfunction "1_1") (pintype "passive"))
    )
    (net (code "40") (name "Net-(IC4A-PE12)") (class "Default")
      (node (ref "IC4") (pin "42") (pinfunction "PE12_42") (pintype "bidirectional"))
      (node (ref "R85") (pin "2") (pinfunction "2_2") (pintype "passive"))
      (node (ref "R89") (pin "1") (pinfunction "1_1") (pintype "passive"))
    )
    (net (code "41") (name "Net-(IC4A-PE13)") (class "Default")
      (node (ref "IC4") (pin "43") (pinfunction "PE13_43") (pintype "bidirectional"))
      (node (ref "R86") (pin "2") (pinfunction "2_2") (pintype "passive"))
      (node (ref "R90") (pin "1") (pinfunction "1_1") (pintype "passive"))
    )
    (net (code "42") (name "Net-(IC4A-PE14)") (class "Default")
      (node (ref "IC4") (pin "44") (pinfunction "PE14_44") (pintype "bidirectional"))
      (node (ref "R87") (pin "2") (pinfunction "2_2") (pintype "passive"))
      (node (ref "R91") (pin "1") (pinfunction "1_1") (pintype "passive"))
    )
    (net (code "43") (name "Net-(IC4A-VCAP_1)") (class "Default")
      (node (ref "C30") (pin "1") (pinfunction "1_1") (pintype "passive"))
      (node (ref "IC4") (pin "48") (pinfunction "VCAP_1_48") (pintype "passive"))
    )
    (net (code "44") (name "Net-(IC4A-VCAP_2)") (class "Default")
      (node (ref "C29") (pin "1") (pinfunction "1_1") (pintype "passive"))
      (node (ref "IC4") (pin "73") (pinfunction "VCAP_2_73") (pintype "passive"))
    )
    (net (code "45") (name "Net-(IC5-C1)") (class "Default")
      (node (ref "C21") (pin "1") (pinfunction "1_1") (pintype "passive"))
      (node (ref "IC5") (pin "4") (pinfunction "C1_4") (pintype "passive"))
    )
    (net (code "46") (name "Net-(IC5-SCL{slash}SPC)") (class "Default")
      (node (ref "IC5") (pin "1") (pinfunction "SCL/SPC_1") (pintype "input"))
      (node (ref "R23") (pin "2") (pinfunction "2_2") (pintype "passive"))
    )
    (net (code "47") (name "Net-(IC5-SDA{slash}SDI{slash}SDO)") (class "Default")
      (node (ref "IC5") (pin "11") (pinfunction "SDA/SDI/SDO_11") (pintype "bidirectional"))
      (node (ref "R24") (pin "2") (pinfunction "2_2") (pintype "passive"))
    )
    (net (code "48") (name "Net-(IC6-SCL{slash}SPC)") (class "Default")
      (node (ref "IC6") (pin "1") (pinfunction "SCL/SPC_1") (pintype "input"))
      (node (ref "R32") (pin "2") (pinfunction "2_2") (pintype "passive"))
    )
    (net (code "49") (name "Net-(IC6-SDA{slash}SDI{slash}SDO)") (class "Default")
      (node (ref "IC6") (pin "4") (pinfunction "SDA/SDI/SDO_4") (pintype "bidirectional"))
      (node (ref "R33") (pin "2") (pinfunction "2_2") (pintype "passive"))
    )
    (net (code "50") (name "Net-(IC7-A0)") (class "Default")
      (node (ref "IC7") (pin "1") (pinfunction "A0_1") (pintype "input"))
      (node (ref "R35") (pin "2") (pinfunction "2_2") (pintype "passive"))
      (node (ref "R41") (pin "1") (pinfunction "1_1") (pintype "passive"))
    )
    (net (code "51") (name "Net-(IC7-A1)") (class "Default")
      (node (ref "IC7") (pin "2") (pinfunction "A1_2") (pintype "input"))
      (node (ref "R36") (pin "2") (pinfunction "2_2") (pintype "passive"))
      (node (ref "R42") (pin "1") (pinfunction "1_1") (pintype "passive"))
    )
    (net (code "52") (name "Net-(IC7-A2)") (class "Default")
      (node (ref "IC7") (pin "3") (pinfunction "A2_3") (pintype "input"))
      (node (ref "R37") (pin "2") (pinfunction "2_2") (pintype "passive"))
      (node (ref "R43") (pin "1") (pinfunction "1_1") (pintype "passive"))
    )
    (net (code "53") (name "Net-(IC7-SCL)") (class "Default")
      (node (ref "C76") (pin "1") (pinfunction "1_1") (pintype "passive"))
      (node (ref "IC7") (pin "6") (pinfunction "SCL_6") (pintype "input"))
      (node (ref "R38") (pin "2") (pinfunction "2_2") (pintype "passive"))
    )
    (net (code "54") (name "Net-(IC7-SDA)") (class "Default")
      (node (ref "C75") (pin "1") (pinfunction "1_1") (pintype "passive"))
      (node (ref "IC7") (pin "5") (pinfunction "SDA_5") (pintype "bidirectional"))
      (node (ref "R39") (pin "2") (pinfunction "2_2") (pintype "passive"))
    )
    (net (code "55") (name "Net-(IC7-WP)") (class "Default")
      (node (ref "IC7") (pin "7") (pinfunction "WP_7") (pintype "input"))
      (node (ref "R34") (pin "2") (pinfunction "2_2") (pintype "passive"))
      (node (ref "R40") (pin "1") (pinfunction "1_1") (pintype "passive"))
    )
    (net (code "56") (name "Net-(X1-CLOCK)") (class "Default")
      (node (ref "R25") (pin "1") (pinfunction "1_1") (pintype "passive"))
      (node (ref "X1") (pin "2") (pinfunction "CLOCK_2") (pintype "passive"))
    )
    (net (code "57") (name "Net-(X2-1_Xtal)") (class "Default")
      (node (ref "C23") (pin "1") (pinfunction "1_1") (pintype "passive"))
      (node (ref "R27") (pin "2") (pinfunction "2_2") (pintype "passive"))
      (node (ref "X2") (pin "1") (pinfunction "1_Xtal_1") (pintype "passive"))
    )
    (net (code "58") (name "Net-(X2-2_Xtal)") (class "Default")
      (node (ref "C24") (pin "2") (pinfunction "2_2") (pintype "passive"))
      (node (ref "R26") (pin "2") (pinfunction "2_2") (pintype "passive"))
      (node (ref "X2") (pin "3") (pinfunction "2_Xtal_3") (pintype "passive"))
    )
    (net (code "59") (name "P3V3") (class "Default")
      (node (ref "C18") (pin "1") (pinfunction "1_1") (pintype "passive"))
      (node (ref "C19") (pin "1") (pinfunction "1_1") (pintype "passive"))
      (node (ref "C22") (pin "1") (pinfunction "1_1") (pintype "passive"))
      (node (ref "C27") (pin "1") (pinfunction "1_1") (pintype "passive"))
      (node (ref "C38") (pin "1") (pinfunction "1_1") (pintype "passive"))
      (node (ref "C39") (pin "1") (pinfunction "1_1") (pintype "passive"))
      (node (ref "IC4") (pin "20") (pinfunction "VREF+_20") (pintype "power_in"))
      (node (ref "IC4") (pin "21") (pinfunction "VDDA_21") (pintype "power_in"))
      (node (ref "IC5") (pin "5") (pinfunction "Vdd_5") (pintype "power_in"))
      (node (ref "IC6") (pin "9") (pinfunction "Vdd_9") (pintype "power_in"))
    )
    (net (code "60") (name "VDD") (class "Default")
      (node (ref "C20") (pin "1") (pinfunction "1_1") (pintype "passive"))
      (node (ref "C28") (pin "1") (pinfunction "1_1") (pintype "passive"))
      (node (ref "C31") (pin "1") (pinfunction "1_1") (pintype "passive"))
      (node (ref "C32") (pin "1") (pinfunction "1_1") (pintype "passive"))
      (node (ref "C33") (pin "1") (pinfunction "1_1") (pintype "passive"))
      (node (ref "C34") (pin "1") (pinfunction "1_1") (pintype "passive"))
      (node (ref "C35") (pin "1") (pinfunction "1_1") (pintype "passive"))
      (node (ref "C36") (pin "1") (pinfunction "1_1") (pintype "passive"))
      (node (ref "C37") (pin "1") (pinfunction "1_1") (pintype "passive"))
      (node (ref "IC4") (pin "100") (pinfunction "VDD_100") (pintype "power_in"))
      (node (ref "IC4") (pin "11") (pinfunction "VDD_11") (pintype "power_in"))
      (node (ref "IC4") (pin "27") (pinfunction "VDD_27") (pintype "power_in"))
      (node (ref "IC4") (pin "50") (pinfunction "VDD_50") (pintype "power_in"))
      (node (ref "IC4") (pin "6") (pinfunction "VBAT_6") (pintype "power_in"))
      (node (ref "IC4") (pin "75") (pinfunction "VDD_75") (pintype "power_in"))
      (node (ref "IC5") (pin "6") (pinfunction "Vdd_IO_6") (pintype "power_in"))
      (node (ref "IC6") (pin "10") (pinfunction "Vdd_IO_10") (pintype "power_in"))
      (node (ref "IC7") (pin "8") (pinfunction "VCC_8") (pintype "power_in"))
      (node (ref "R19") (pin "2") (pinfunction "2_2") (pintype "passive"))
      (node (ref "R20") (pin "2") (pinfunction "2_2") (pintype "passive"))
      (node (ref "R21") (pin "2") (pinfunction "2_2") (pintype "passive"))
      (node (ref "R22") (pin "2") (pinfunction "2_2") (pintype "passive"))
      (node (ref "R28") (pin "2") (pinfunction "2_2") (pintype "passive"))
      (node (ref "R30") (pin "2") (pinfunction "2_2") (pintype "passive"))
      (node (ref "R31") (pin "2") (pinfunction "2_2") (pintype "passive"))
      (node (ref "R34") (pin "1") (pinfunction "1_1") (pintype "passive"))
      (node (ref "R35") (pin "1") (pinfunction "1_1") (pintype "passive"))
      (node (ref "R36") (pin "1") (pinfunction "1_1") (pintype "passive"))
      (node (ref "R37") (pin "1") (pinfunction "1_1") (pintype "passive"))
      (node (ref "R84") (pin "1") (pinfunction "1_1") (pintype "passive"))
      (node (ref "R85") (pin "1") (pinfunction "1_1") (pintype "passive"))
      (node (ref "R86") (pin "1") (pinfunction "1_1") (pintype "passive"))
      (node (ref "R87") (pin "1") (pinfunction "1_1") (pintype "passive"))
      (node (ref "X1") (pin "1") (pinfunction "V+_1") (pintype "passive"))
    )
    (net (code "61") (name "unconnected-(IC4A-PA3-Pad25)") (class "Default")
      (node (ref "IC4") (pin "25") (pinfunction "PA3_25") (pintype "bidirectional"))
    )
    (net (code "62") (name "unconnected-(IC4A-PA5-Pad29)") (class "Default")
      (node (ref "IC4") (pin "29") (pinfunction "PA5_29") (pintype "bidirectional"))
    )
    (net (code "63") (name "unconnected-(IC4A-PA6-Pad30)") (class "Default")
      (node (ref "IC4") (pin "30") (pinfunction "PA6_30") (pintype "bidirectional"))
    )
    (net (code "64") (name "unconnected-(IC4A-PA7-Pad31)") (class "Default")
      (node (ref "IC4") (pin "31") (pinfunction "PA7_31") (pintype "bidirectional"))
    )
    (net (code "65") (name "unconnected-(IC4A-PA12-Pad71)") (class "Default")
      (node (ref "IC4") (pin "71") (pinfunction "PA12_71") (pintype "bidirectional"))
    )
    (net (code "66") (name "unconnected-(IC4A-PB0-Pad34)") (class "Default")
      (node (ref "IC4") (pin "34") (pinfunction "PB0_34") (pintype "bidirectional"))
    )
    (net (code "67") (name "unconnected-(IC4A-PB1-Pad35)") (class "Default")
      (node (ref "IC4") (pin "35") (pinfunction "PB1_35") (pintype "bidirectional"))
    )
    (net (code "68") (name "unconnected-(IC4A-PB2-Pad36)") (class "Default")
      (node (ref "IC4") (pin "36") (pinfunction "PB2_36") (pintype "bidirectional"))
    )
    (net (code "69") (name "unconnected-(IC4A-PB12-Pad51)") (class "Default")
      (node (ref "IC4") (pin "51") (pinfunction "PB12_51") (pintype "bidirectional"))
    )
    (net (code "70") (name "unconnected-(IC4A-PB13-Pad52)") (class "Default")
      (node (ref "IC4") (pin "52") (pinfunction "PB13_52") (pintype "bidirectional"))
    )
    (net (code "71") (name "unconnected-(IC4A-PB14-Pad53)") (class "Default")
      (node (ref "IC4") (pin "53") (pinfunction "PB14_53") (pintype "bidirectional"))
    )
    (net (code "72") (name "unconnected-(IC4A-PB15-Pad54)") (class "Default")
      (node (ref "IC4") (pin "54") (pinfunction "PB15_54") (pintype "bidirectional"))
    )
    (net (code "73") (name "unconnected-(IC4A-PC3-Pad18)") (class "Default")
      (node (ref "IC4") (pin "18") (pinfunction "PC3_18") (pintype "bidirectional"))
    )
    (net (code "74") (name "unconnected-(IC4A-PC4-Pad32)") (class "Default")
      (node (ref "IC4") (pin "32") (pinfunction "PC4_32") (pintype "bidirectional"))
    )
    (net (code "75") (name "unconnected-(IC4A-PC5-Pad33)") (class "Default")
      (node (ref "IC4") (pin "33") (pinfunction "PC5_33") (pintype "bidirectional"))
    )
    (net (code "76") (name "unconnected-(IC4A-PC6-Pad63)") (class "Default")
      (node (ref "IC4") (pin "63") (pinfunction "PC6_63") (pintype "bidirectional"))
    )
    (net (code "77") (name "unconnected-(IC4A-PC7-Pad64)") (class "Default")
      (node (ref "IC4") (pin "64") (pinfunction "PC7_64") (pintype "bidirectional"))
    )
    (net (code "78") (name "unconnected-(IC4A-PC8-Pad65)") (class "Default")
      (node (ref "IC4") (pin "65") (pinfunction "PC8_65") (pintype "bidirectional"))
    )
    (net (code "79") (name "unconnected-(IC4A-PC10-Pad78)") (class "Default")
      (node (ref "IC4") (pin "78") (pinfunction "PC10_78") (pintype "bidirectional"))
    )
    (net (code "80") (name "unconnected-(IC4A-PC11-Pad79)") (class "Default")
      (node (ref "IC4") (pin "79") (pinfunction "PC11_79") (pintype "bidirectional"))
    )
    (net (code "81") (name "unconnected-(IC4A-PC12-Pad80)") (class "Default")
      (node (ref "IC4") (pin "80") (pinfunction "PC12_80") (pintype "bidirectional"))
    )
    (net (code "82") (name "unconnected-(IC4A-PC13-Pad7)") (class "Default")
      (node (ref "IC4") (pin "7") (pinfunction "PC13_7") (pintype "bidirectional"))
    )
    (net (code "83") (name "unconnected-(IC4A-PC14-OSC32_IN(PC14)-Pad8)") (class "Default")
      (node (ref "IC4") (pin "8") (pinfunction "PC14-OSC32_IN(PC14)_8") (pintype "bidirectional"))
    )
    (net (code "84") (name "unconnected-(IC4A-PC15-OSC32_OUT(PC15)-Pad9)") (class "Default")
      (node (ref "IC4") (pin "9") (pinfunction "PC15-OSC32_OUT(PC15)_9") (pintype "bidirectional"))
    )
    (net (code "85") (name "unconnected-(IC4A-PD0-Pad81)") (class "Default")
      (node (ref "IC4") (pin "81") (pinfunction "PD0_81") (pintype "bidirectional"))
    )
    (net (code "86") (name "unconnected-(IC4A-PD1-Pad82)") (class "Default")
      (node (ref "IC4") (pin "82") (pinfunction "PD1_82") (pintype "bidirectional"))
    )
    (net (code "87") (name "unconnected-(IC4A-PD2-Pad83)") (class "Default")
      (node (ref "IC4") (pin "83") (pinfunction "PD2_83") (pintype "bidirectional"))
    )
    (net (code "88") (name "unconnected-(IC4A-PD3-Pad84)") (class "Default")
      (node (ref "IC4") (pin "84") (pinfunction "PD3_84") (pintype "bidirectional"))
    )
    (net (code "89") (name "unconnected-(IC4A-PD4-Pad85)") (class "Default")
      (node (ref "IC4") (pin "85") (pinfunction "PD4_85") (pintype "bidirectional"))
    )
    (net (code "90") (name "unconnected-(IC4A-PD5-Pad86)") (class "Default")
      (node (ref "IC4") (pin "86") (pinfunction "PD5_86") (pintype "bidirectional"))
    )
    (net (code "91") (name "unconnected-(IC4A-PD6-Pad87)") (class "Default")
      (node (ref "IC4") (pin "87") (pinfunction "PD6_87") (pintype "bidirectional"))
    )
    (net (code "92") (name "unconnected-(IC4A-PD7-Pad88)") (class "Default")
      (node (ref "IC4") (pin "88") (pinfunction "PD7_88") (pintype "bidirectional"))
    )
    (net (code "93") (name "unconnected-(IC4A-PD8-Pad55)") (class "Default")
      (node (ref "IC4") (pin "55") (pinfunction "PD8_55") (pintype "bidirectional"))
    )
    (net (code "94") (name "unconnected-(IC4A-PD9-Pad56)") (class "Default")
      (node (ref "IC4") (pin "56") (pinfunction "PD9_56") (pintype "bidirectional"))
    )
    (net (code "95") (name "unconnected-(IC4A-PD10-Pad57)") (class "Default")
      (node (ref "IC4") (pin "57") (pinfunction "PD10_57") (pintype "bidirectional"))
    )
    (net (code "96") (name "unconnected-(IC4A-PD11-Pad58)") (class "Default")
      (node (ref "IC4") (pin "58") (pinfunction "PD11_58") (pintype "bidirectional"))
    )
    (net (code "97") (name "unconnected-(IC4A-PD12-Pad59)") (class "Default")
      (node (ref "IC4") (pin "59") (pinfunction "PD12_59") (pintype "bidirectional"))
    )
    (net (code "98") (name "unconnected-(IC4A-PD13-Pad60)") (class "Default")
      (node (ref "IC4") (pin "60") (pinfunction "PD13_60") (pintype "bidirectional"))
    )
    (net (code "99") (name "unconnected-(IC4A-PD14-Pad61)") (class "Default")
      (node (ref "IC4") (pin "61") (pinfunction "PD14_61") (pintype "bidirectional"))
    )
    (net (code "100") (name "unconnected-(IC4A-PD15-Pad62)") (class "Default")
      (node (ref "IC4") (pin "62") (pinfunction "PD15_62") (pintype "bidirectional"))
    )
    (net (code "101") (name "unconnected-(IC4A-PE0-Pad97)") (class "Default")
      (node (ref "IC4") (pin "97") (pinfunction "PE0_97") (pintype "bidirectional"))
    )
    (net (code "102") (name "unconnected-(IC4A-PE1-Pad98)") (class "Default")
      (node (ref "IC4") (pin "98") (pinfunction "PE1_98") (pintype "bidirectional"))
    )
    (net (code "103") (name "unconnected-(IC4A-PE3-Pad2)") (class "Default")
      (node (ref "IC4") (pin "2") (pinfunction "PE3_2") (pintype "bidirectional"))
    )
    (net (code "104") (name "unconnected-(IC4A-PE15-Pad45)") (class "Default")
      (node (ref "IC4") (pin "45") (pinfunction "PE15_45") (pintype "bidirectional"))
    )
    (net (code "105") (name "unconnected-(IC5-SD0{slash}SA1-Pad9)") (class "Default")
      (node (ref "IC5") (pin "9") (pinfunction "SD0/SA1_9") (pintype "bidirectional"))
    )
    (net (code "106") (name "unconnected-(IC6-NC-Pad5)") (class "Default")
      (node (ref "IC6") (pin "5") (pinfunction "NC_5") (pintype "passive"))
    )
    (net (code "107") (name "unconnected-(IC6-SD0{slash}SA1-Pad3)") (class "Default")
      (node (ref "IC6") (pin "3") (pinfunction "SD0/SA1_3") (pintype "bidirectional"))
    )
  )
)
